# Main_Trigger.net
KiCad netlist of a schematic drawn in Altium Designer
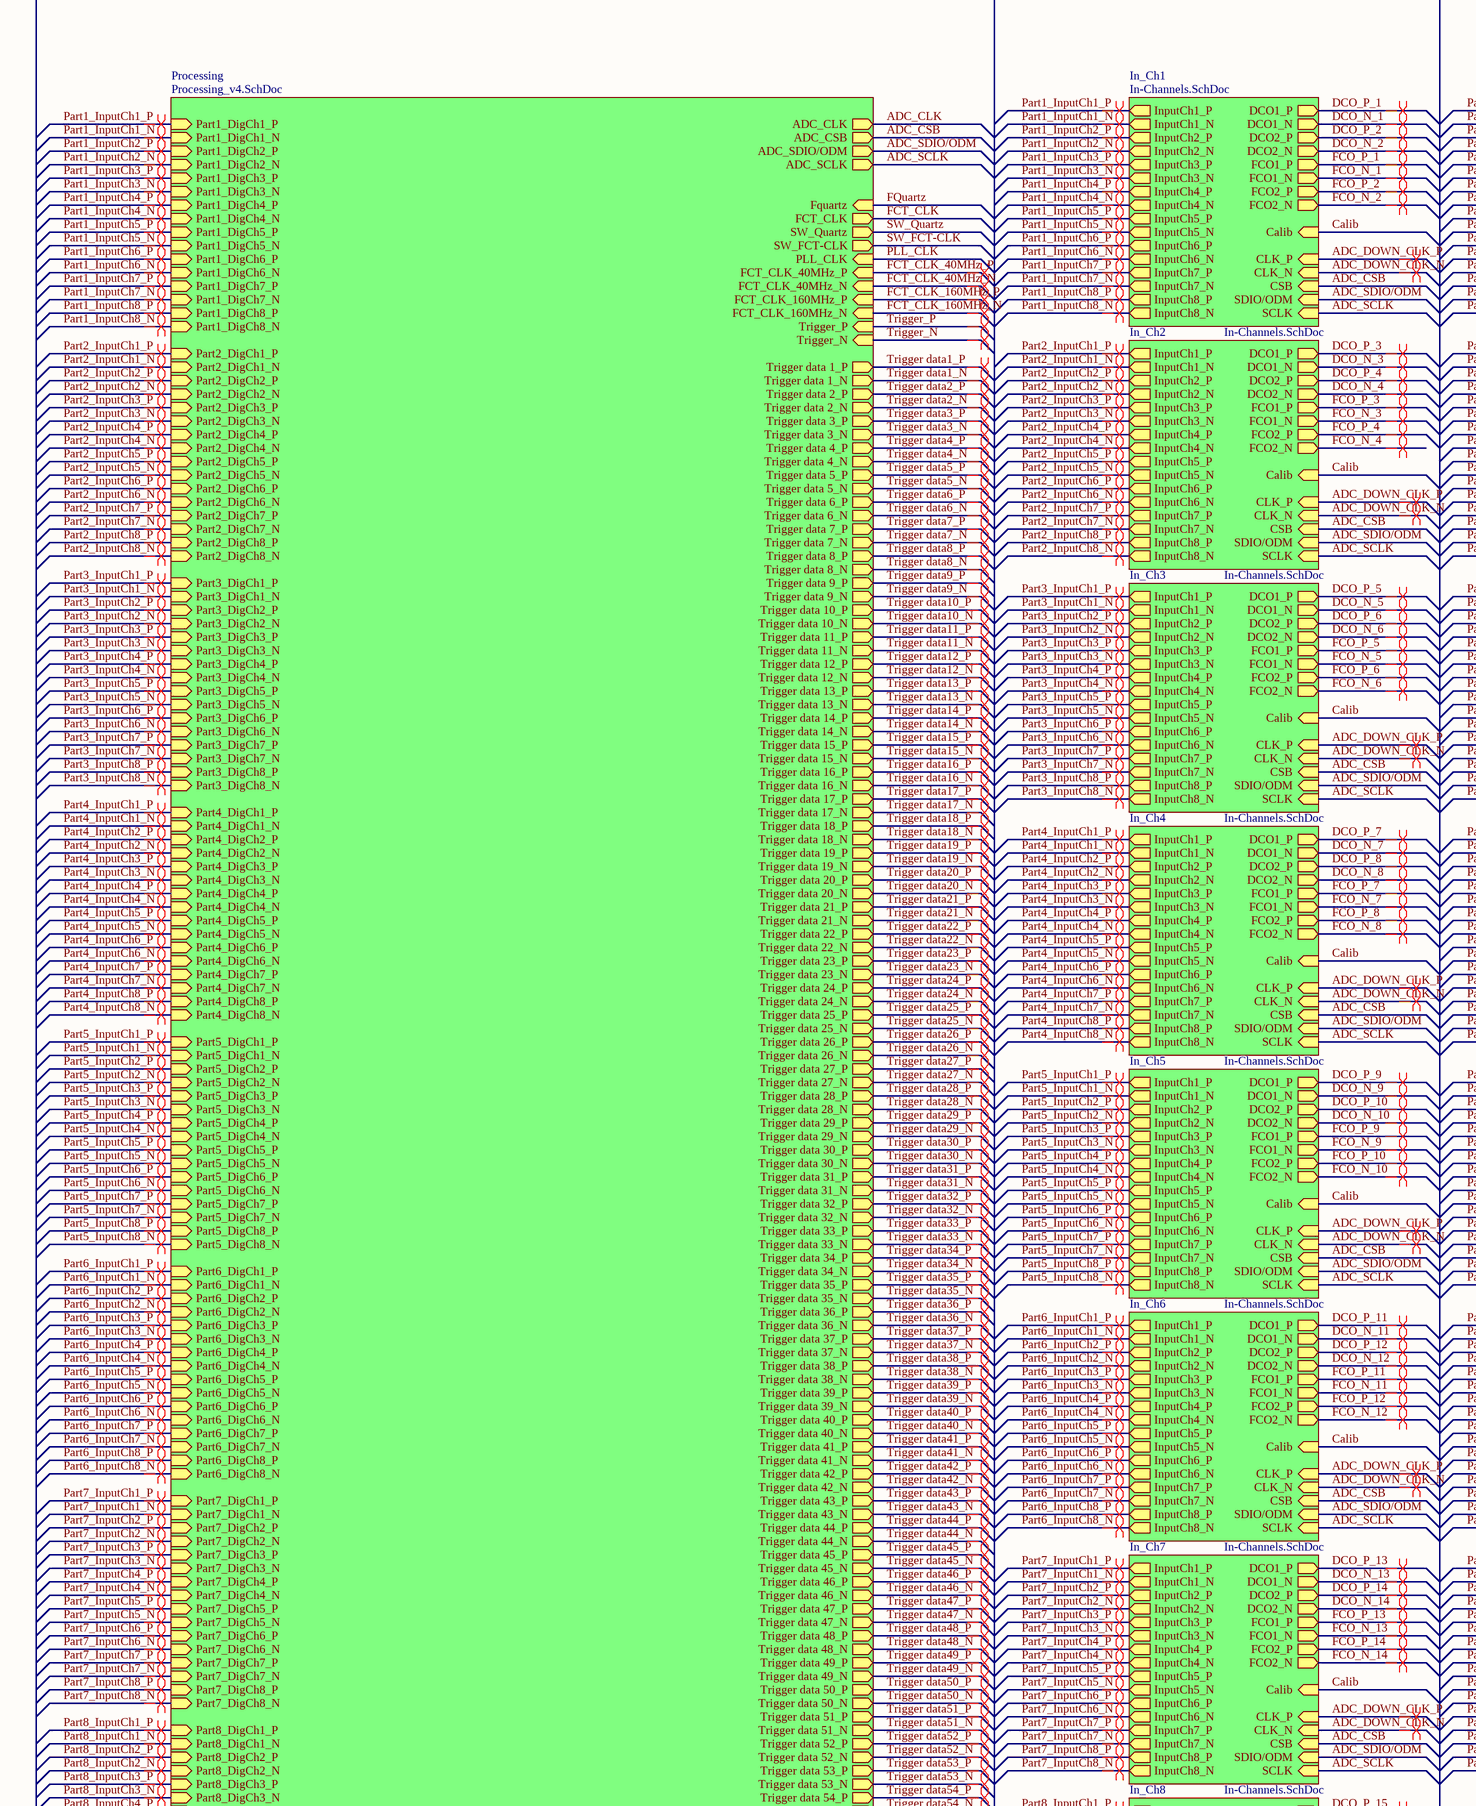
[diagram p0: Main_Trigger.SchDoc, top left]
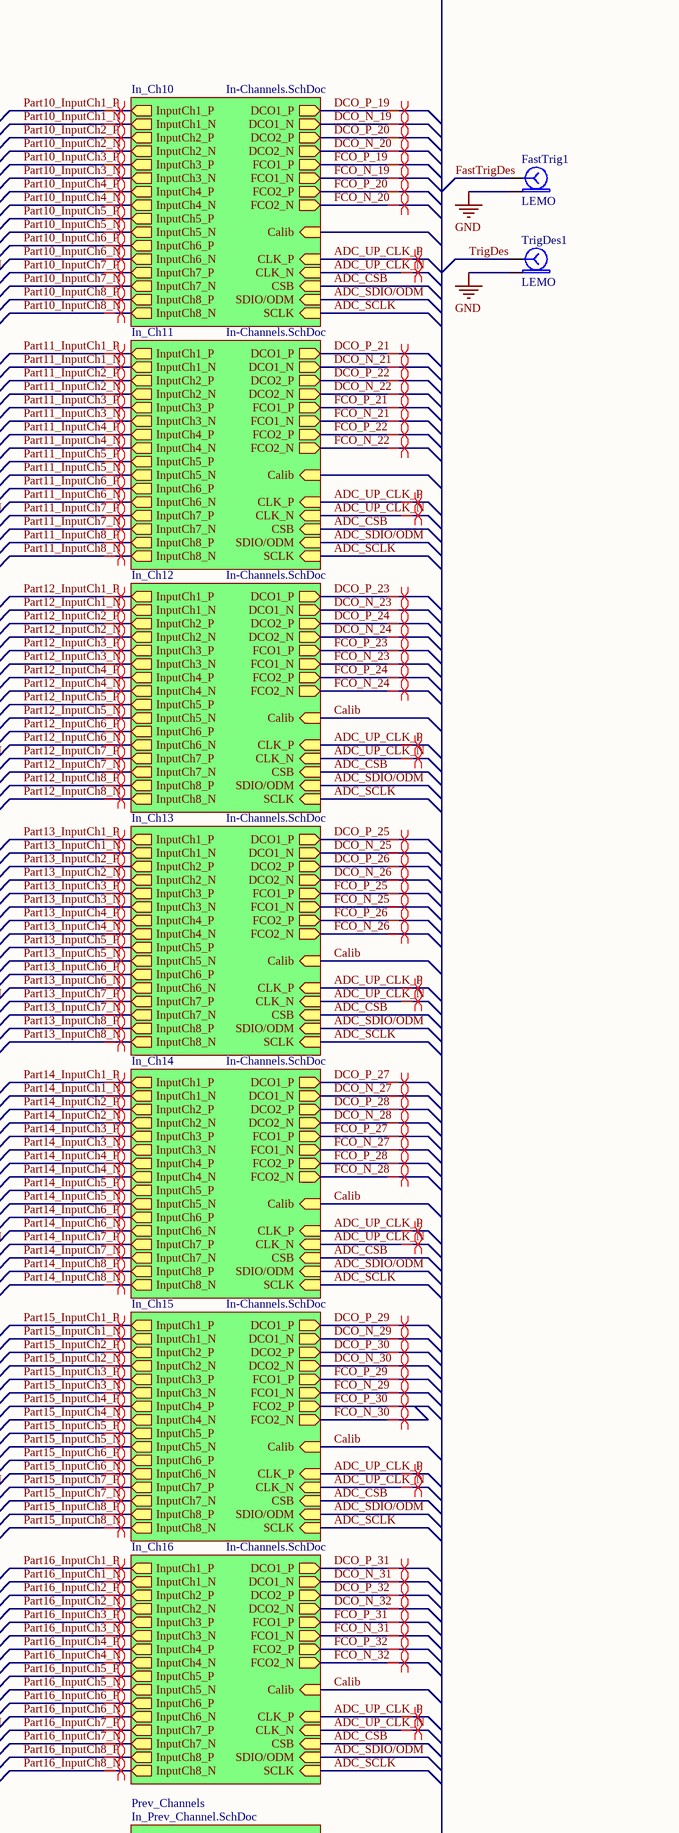
[diagram p1: Main_Trigger.SchDoc, top middle]
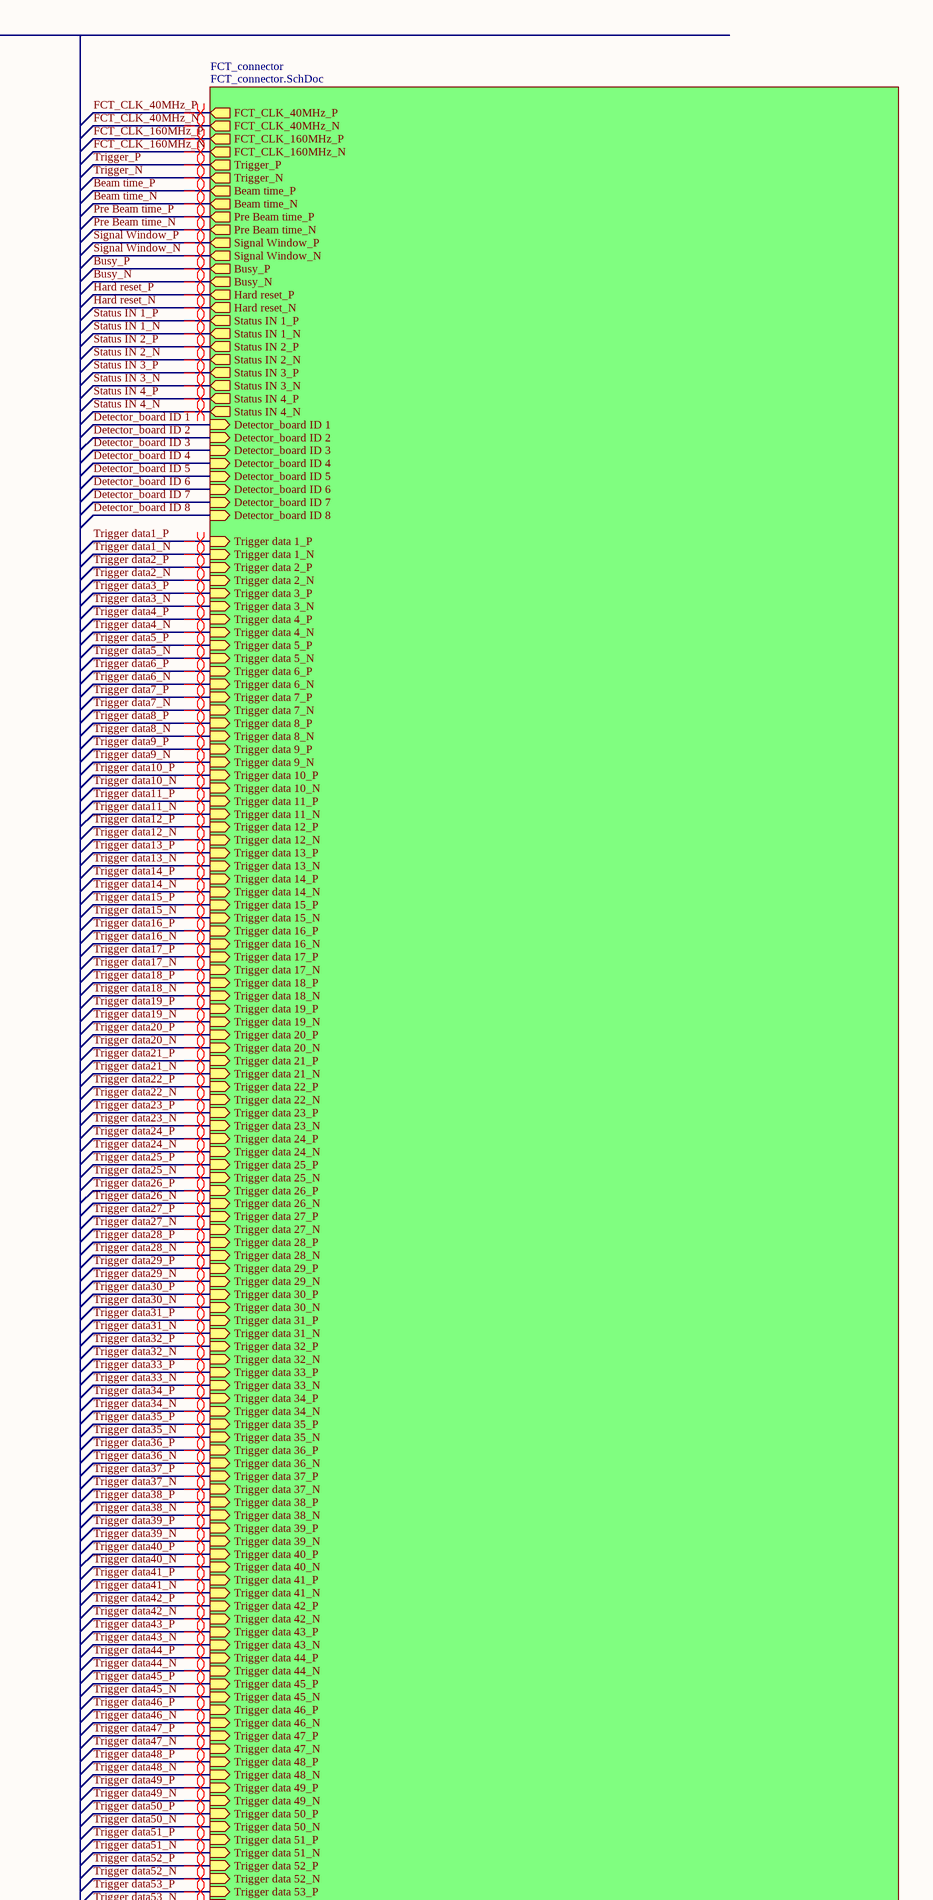
[diagram p2: Main_Trigger.SchDoc, top right]
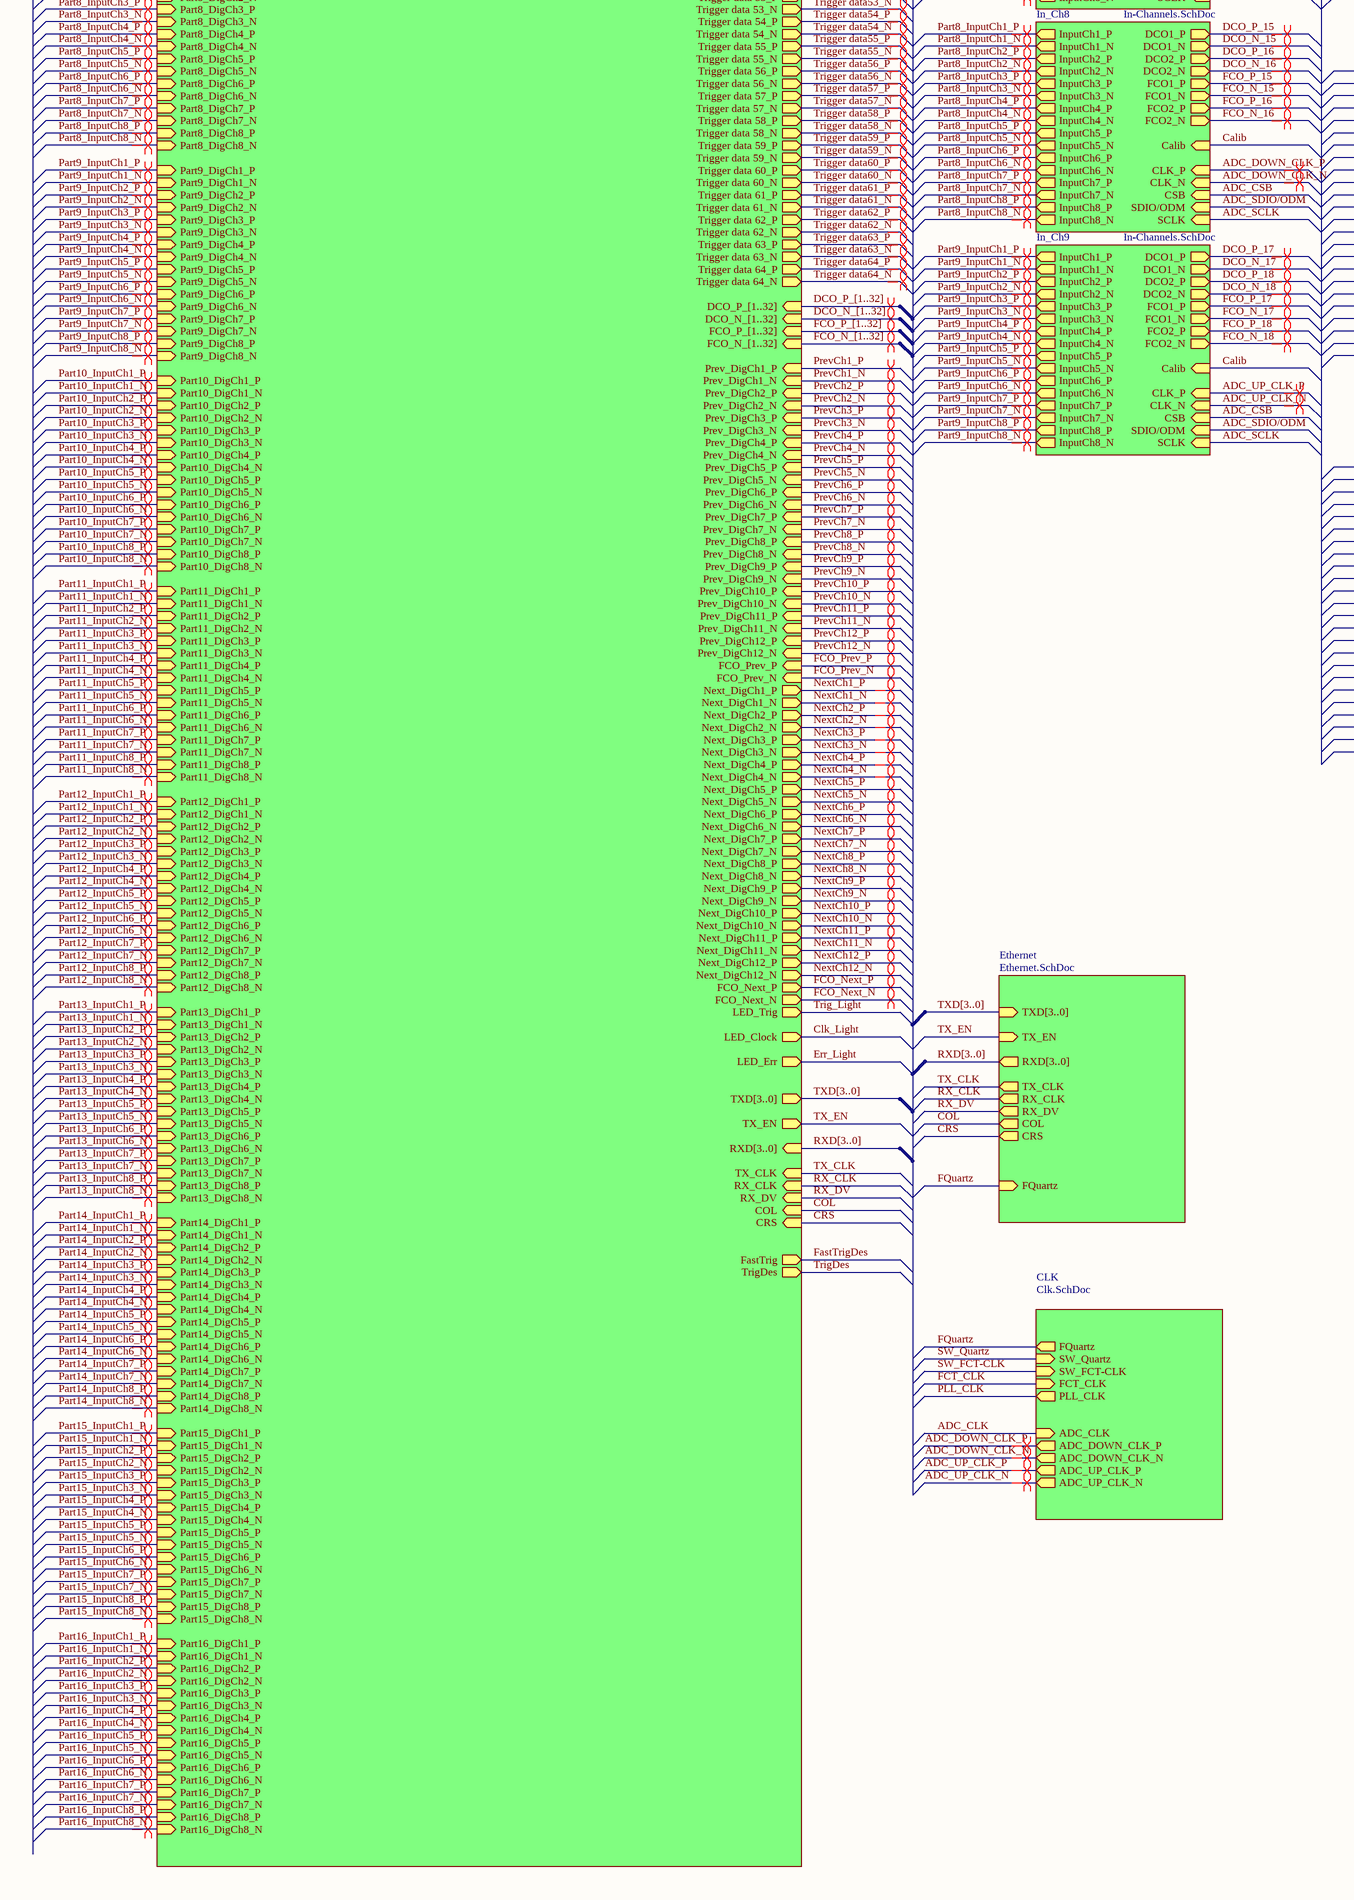
[diagram p3: Main_Trigger.SchDoc, bottom left]
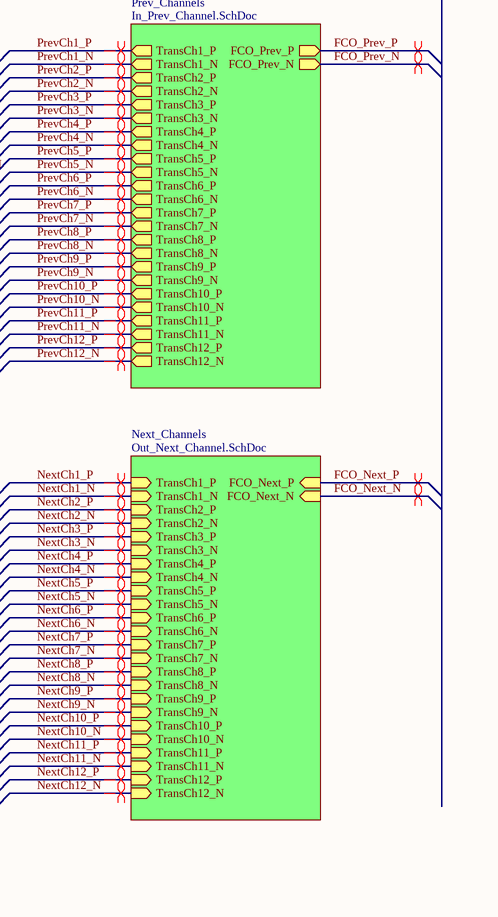
[diagram p4: Main_Trigger.SchDoc, bottom middle]
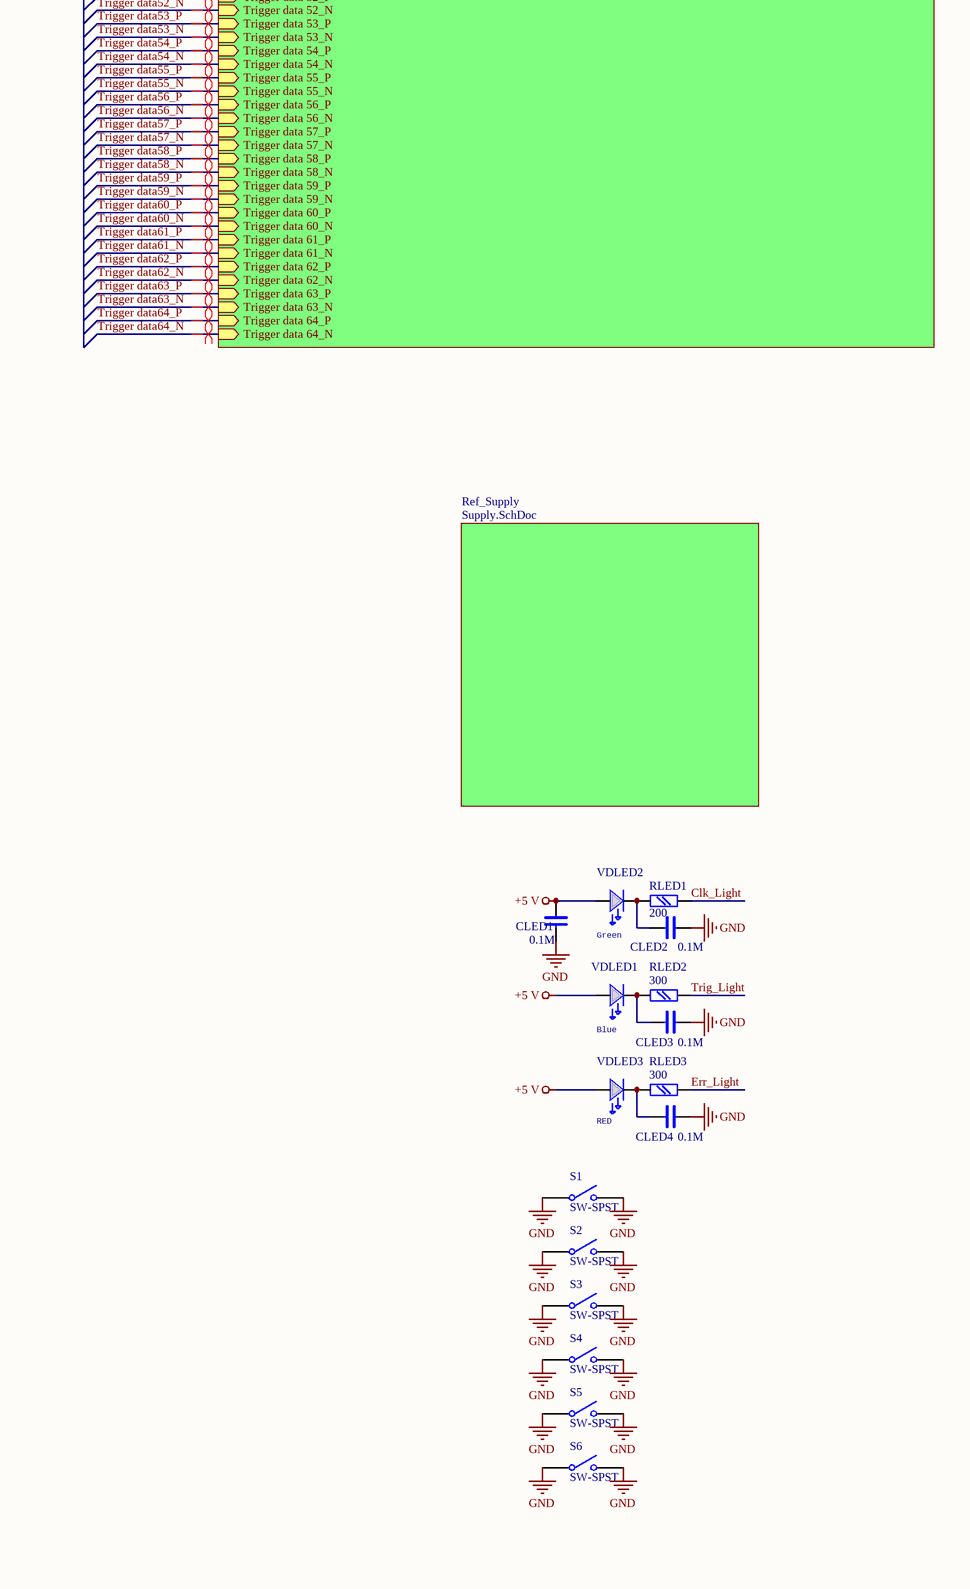
[diagram p5: Main_Trigger.SchDoc, bottom right]

(export (version "E")
  (design (tool "Eeschema 10.0.6"))
  (components
    (comp (ref "CLED1") (value "0.1M") (footprint "chip0805") (libsource (lib "*") (part "C")))
    (comp (ref "CLED2") (value "0.1M") (footprint "chip0805") (libsource (lib "*") (part "C")))
    (comp (ref "CLED3") (value "0.1M") (footprint "chip0805") (libsource (lib "*") (part "C")))
    (comp (ref "CLED4") (value "0.1M") (footprint "chip0805") (libsource (lib "*") (part "C")))
    (comp (ref "FastTrig1") (value "LEMO") (footprint "LEMO") (libsource (lib "vDevice") (part "LEMO")))
    (comp (ref "RLED1") (value "200") (footprint "chip0805") (libsource (lib "*") (part "R")))
    (comp (ref "RLED2") (value "300") (footprint "chip0805") (libsource (lib "*") (part "R")))
    (comp (ref "RLED3") (value "300") (footprint "chip0805") (libsource (lib "*") (part "R")))
    (comp (ref "S1")
      (value "SW-SPST")
      (footprint "SPST-2")
      (description "Single-Pole, Single-Throw Switch")
      (fields (field (name "PUBLISHER") "Altium Limited"))
      (libsource (lib "Miscellaneous Devices") (part "SW-SPST"))
    )
    (comp (ref "S2")
      (value "SW-SPST")
      (footprint "SPST-2")
      (description "Single-Pole, Single-Throw Switch")
      (fields (field (name "PUBLISHER") "Altium Limited"))
      (libsource (lib "Miscellaneous Devices") (part "SW-SPST"))
    )
    (comp (ref "S3")
      (value "SW-SPST")
      (footprint "SPST-2")
      (description "Single-Pole, Single-Throw Switch")
      (fields (field (name "PUBLISHER") "Altium Limited"))
      (libsource (lib "Miscellaneous Devices") (part "SW-SPST"))
    )
    (comp (ref "S4")
      (value "SW-SPST")
      (footprint "SPST-2")
      (description "Single-Pole, Single-Throw Switch")
      (fields (field (name "PUBLISHER") "Altium Limited"))
      (libsource (lib "Miscellaneous Devices") (part "SW-SPST"))
    )
    (comp (ref "S5")
      (value "SW-SPST")
      (footprint "SPST-2")
      (description "Single-Pole, Single-Throw Switch")
      (fields (field (name "PUBLISHER") "Altium Limited"))
      (libsource (lib "Miscellaneous Devices") (part "SW-SPST"))
    )
    (comp (ref "S6")
      (value "SW-SPST")
      (footprint "SPST-2")
      (description "Single-Pole, Single-Throw Switch")
      (fields (field (name "PUBLISHER") "Altium Limited"))
      (libsource (lib "Miscellaneous Devices") (part "SW-SPST"))
    )
    (comp (ref "TrigDes1") (value "LEMO") (footprint "LEMO") (libsource (lib "vDevice") (part "LEMO")))
    (comp (ref "VDLED1") (value "LED") (footprint "CHIP1206") (libsource (lib "*") (part "AL307")))
    (comp (ref "VDLED2") (value "LED") (footprint "CHIP0805") (libsource (lib "*") (part "AL307")))
    (comp (ref "VDLED3") (value "LED") (footprint "CHIP1206") (libsource (lib "*") (part "AL307")))
  )
  (nets
    (net (code "9") (name "+5 V") (class "Default")
      (node (ref "CLED1") (pin "1") (pinfunction "1_1") (pintype "passive"))
      (node (ref "VDLED1") (pin "ANOD") (pinfunction "ANOD_ANOD") (pintype "passive"))
      (node (ref "VDLED2") (pin "ANOD") (pinfunction "ANOD_ANOD") (pintype "passive"))
      (node (ref "VDLED3") (pin "ANOD") (pinfunction "ANOD_ANOD") (pintype "passive"))
    )
    (net (code "27") (name "/Clk_Light") (class "Default")
      (node (ref "RLED1") (pin "2") (pinfunction "2_2") (pintype "passive"))
    )
    (net (code "102") (name "/Err_Light") (class "Default")
      (node (ref "RLED3") (pin "2") (pinfunction "2_2") (pintype "passive"))
    )
    (net (code "179") (name "/FastTrigDes") (class "Default")
      (node (ref "FastTrig1") (pin "WIRE") (pinfunction "WIRE_WIRE") (pintype "bidirectional"))
    )
    (net (code "507") (name "/TrigDes") (class "Default")
      (node (ref "TrigDes1") (pin "WIRE") (pinfunction "WIRE_WIRE") (pintype "bidirectional"))
    )
    (net (code "508") (name "/Trig_Light") (class "Default")
      (node (ref "RLED2") (pin "2") (pinfunction "2_2") (pintype "passive"))
    )
    (net (code "639") (name "GND") (class "Default")
      (node (ref "CLED1") (pin "2") (pinfunction "2_2") (pintype "passive"))
      (node (ref "CLED2") (pin "2") (pinfunction "2_2") (pintype "passive"))
      (node (ref "CLED3") (pin "2") (pinfunction "2_2") (pintype "passive"))
      (node (ref "CLED4") (pin "2") (pinfunction "2_2") (pintype "passive"))
      (node (ref "FastTrig1") (pin "SHIELD") (pinfunction "SHIELD_SHIELD") (pintype "bidirectional"))
      (node (ref "S1") (pin "1") (pinfunction "COMMON_1") (pintype "passive"))
      (node (ref "S1") (pin "2") (pinfunction "NO_2") (pintype "passive"))
      (node (ref "S2") (pin "1") (pinfunction "COMMON_1") (pintype "passive"))
      (node (ref "S2") (pin "2") (pinfunction "NO_2") (pintype "passive"))
      (node (ref "S3") (pin "1") (pinfunction "COMMON_1") (pintype "passive"))
      (node (ref "S3") (pin "2") (pinfunction "NO_2") (pintype "passive"))
      (node (ref "S4") (pin "1") (pinfunction "COMMON_1") (pintype "passive"))
      (node (ref "S4") (pin "2") (pinfunction "NO_2") (pintype "passive"))
      (node (ref "S5") (pin "1") (pinfunction "COMMON_1") (pintype "passive"))
      (node (ref "S5") (pin "2") (pinfunction "NO_2") (pintype "passive"))
      (node (ref "S6") (pin "1") (pinfunction "COMMON_1") (pintype "passive"))
      (node (ref "S6") (pin "2") (pinfunction "NO_2") (pintype "passive"))
      (node (ref "TrigDes1") (pin "SHIELD") (pinfunction "SHIELD_SHIELD") (pintype "bidirectional"))
    )
    (net (code "640") (name "Net-(CLED2-Pad1)") (class "Default")
      (node (ref "CLED2") (pin "1") (pinfunction "1_1") (pintype "passive"))
      (node (ref "RLED1") (pin "1") (pinfunction "1_1") (pintype "passive"))
      (node (ref "VDLED2") (pin "CATH") (pinfunction "CATH_CATH") (pintype "passive"))
    )
    (net (code "641") (name "Net-(CLED3-Pad1)") (class "Default")
      (node (ref "CLED3") (pin "1") (pinfunction "1_1") (pintype "passive"))
      (node (ref "RLED2") (pin "1") (pinfunction "1_1") (pintype "passive"))
      (node (ref "VDLED1") (pin "CATH") (pinfunction "CATH_CATH") (pintype "passive"))
    )
    (net (code "642") (name "Net-(CLED4-Pad1)") (class "Default")
      (node (ref "CLED4") (pin "1") (pinfunction "1_1") (pintype "passive"))
      (node (ref "RLED3") (pin "1") (pinfunction "1_1") (pintype "passive"))
      (node (ref "VDLED3") (pin "CATH") (pinfunction "CATH_CATH") (pintype "passive"))
    )
  )
)
